# Lemming_SMD_2_2.net
KiCad netlist of a schematic drawn in EAGLE
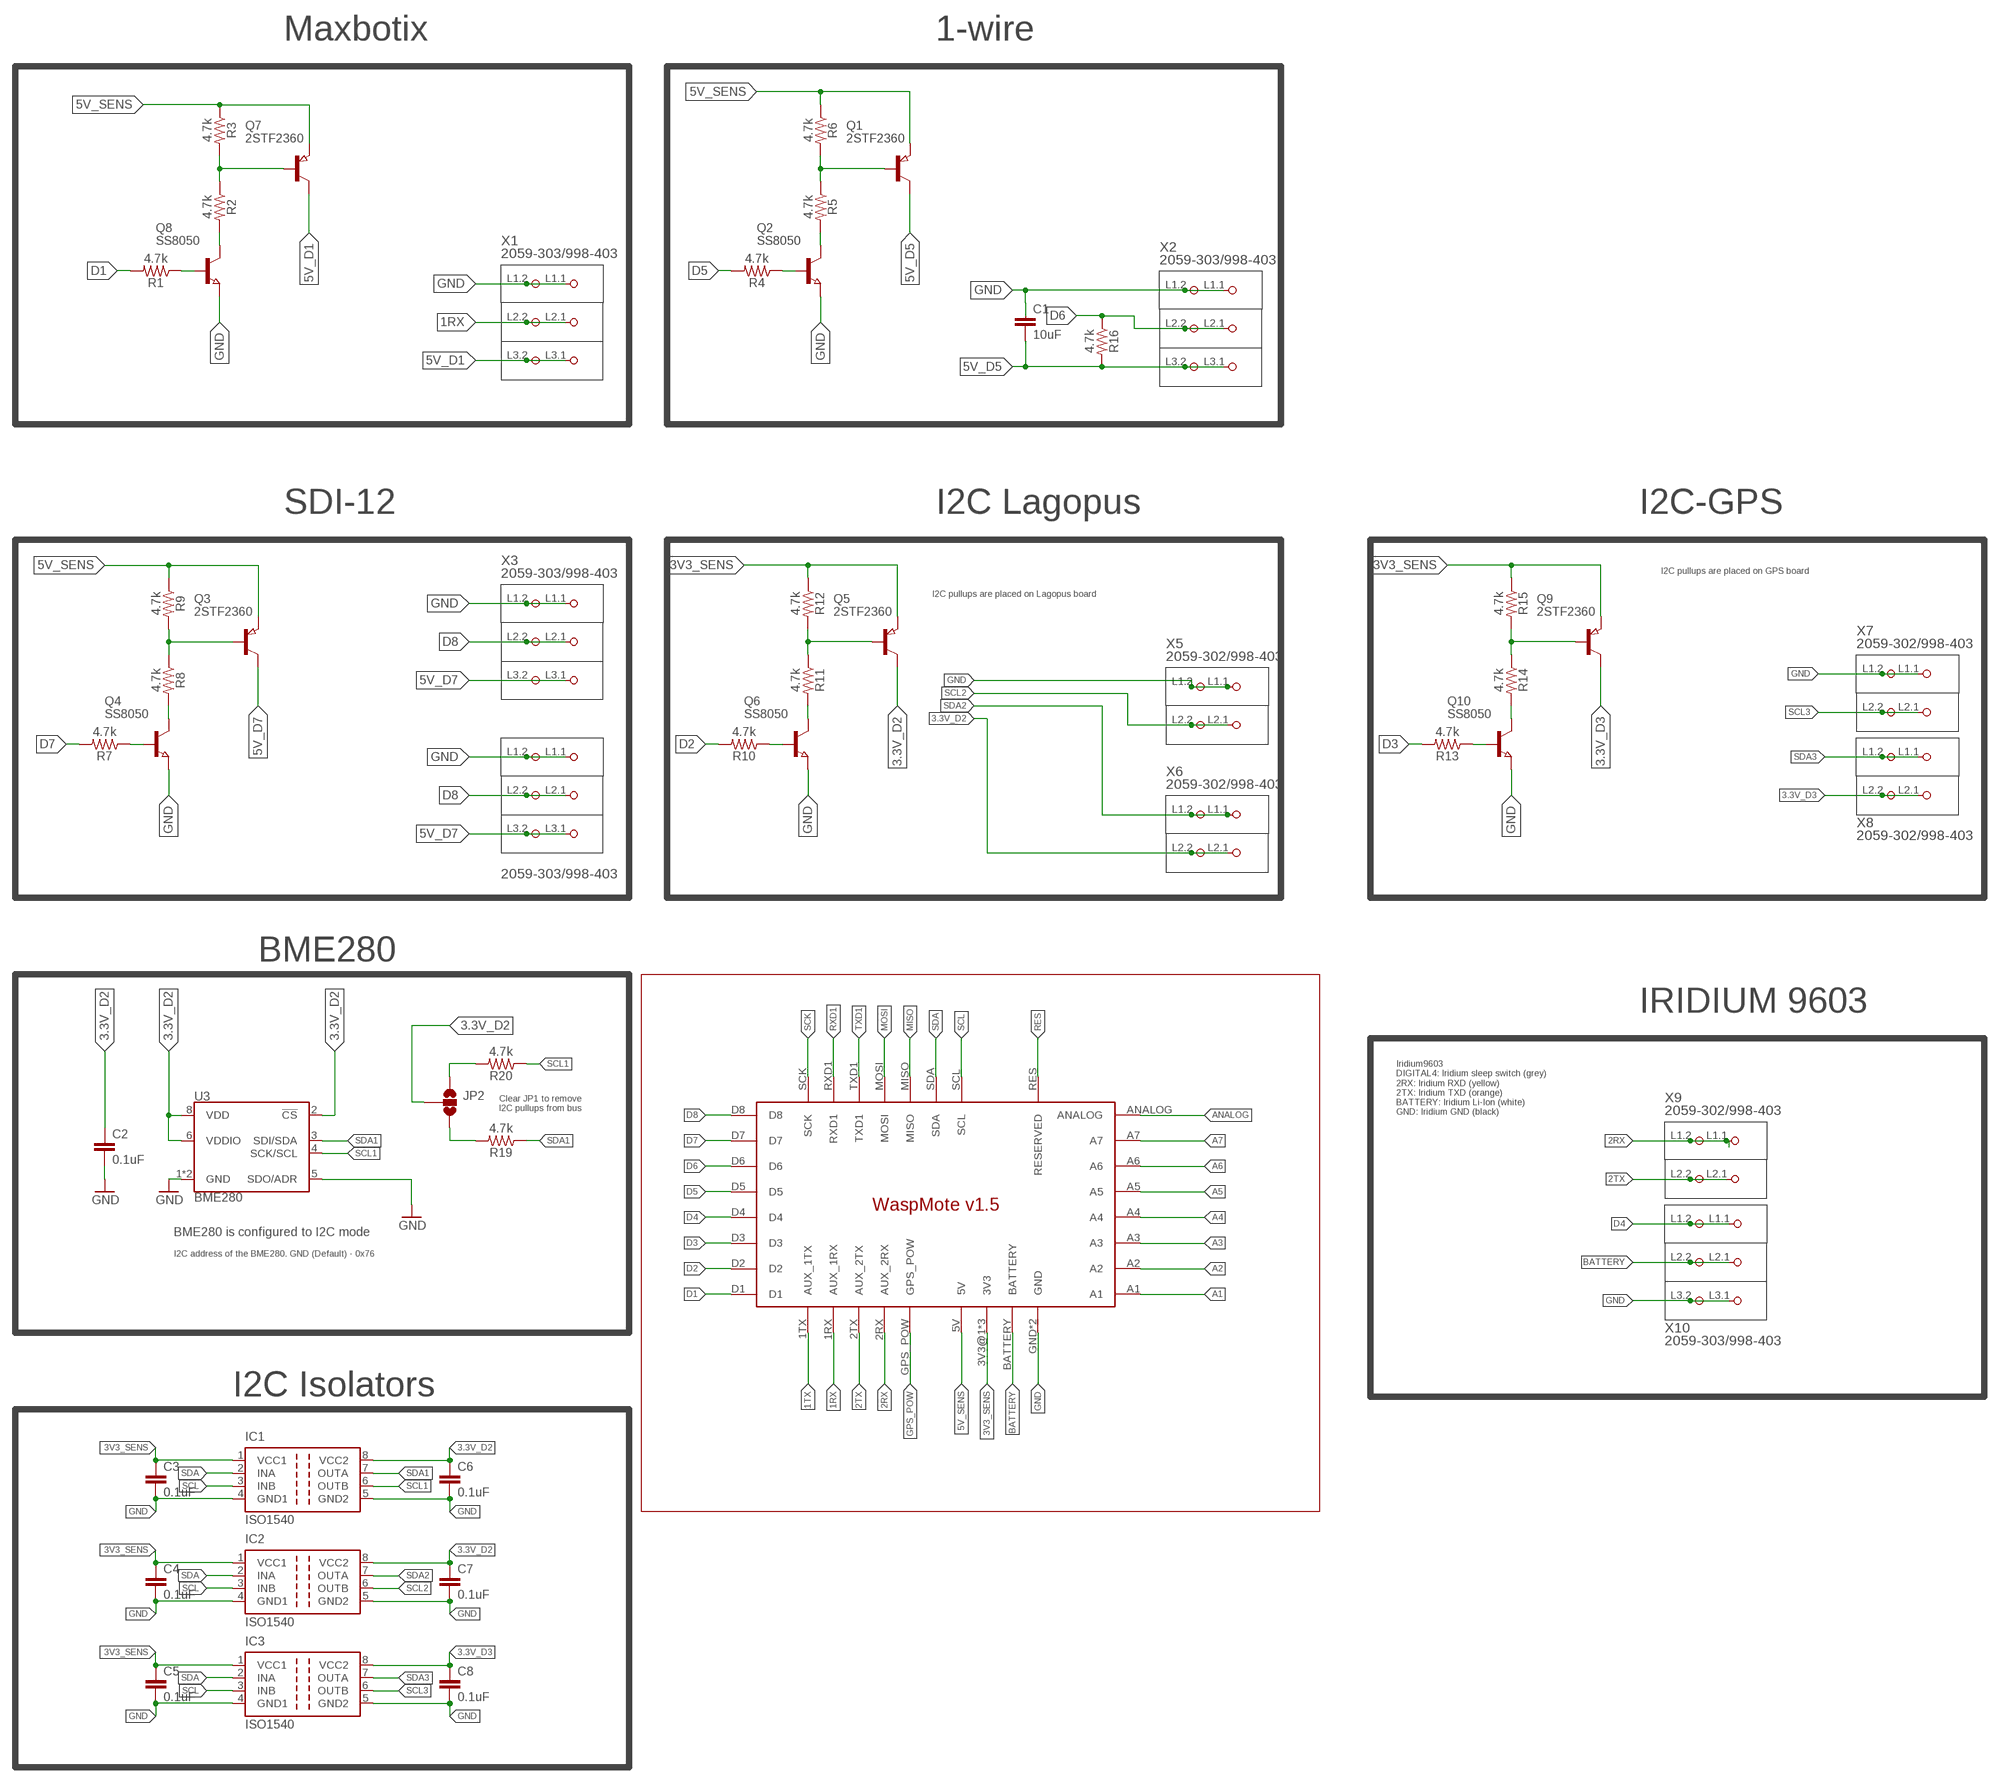
[diagram p0: schematic, sheet 1]

(export (version "E")
  (design (tool "Eeschema 10.0.6"))
  (components
    (comp (ref "C1")
      (value "10uF")
      (footprint "eagle-import:0603")
      (libsource (lib "eagle-import") (part "10UF-0603-6.3V-20%"))
    )
    (comp (ref "C2")
      (value "0.1uF")
      (footprint "eagle-import:0603")
      (libsource (lib "eagle-import") (part "0.1UF-0603-25V-(+80/-20%)"))
    )
    (comp (ref "C3")
      (value "0.1uF")
      (footprint "eagle-import:0603")
      (libsource (lib "eagle-import") (part "0.1UF-0603-25V-(+80/-20%)"))
    )
    (comp (ref "C4")
      (value "0.1uF")
      (footprint "eagle-import:0603")
      (libsource (lib "eagle-import") (part "0.1UF-0603-25V-(+80/-20%)"))
    )
    (comp (ref "C5")
      (value "0.1uF")
      (footprint "eagle-import:0603")
      (libsource (lib "eagle-import") (part "0.1UF-0603-25V-(+80/-20%)"))
    )
    (comp (ref "C6")
      (value "0.1uF")
      (footprint "eagle-import:0603")
      (libsource (lib "eagle-import") (part "0.1UF-0603-25V-(+80/-20%)"))
    )
    (comp (ref "C7")
      (value "0.1uF")
      (footprint "eagle-import:0603")
      (libsource (lib "eagle-import") (part "0.1UF-0603-25V-(+80/-20%)"))
    )
    (comp (ref "C8")
      (value "0.1uF")
      (footprint "eagle-import:0603")
      (libsource (lib "eagle-import") (part "0.1UF-0603-25V-(+80/-20%)"))
    )
    (comp (ref "IC1")
      (value "ISO1540")
      (footprint "eagle-import:SO-08")
      (fields (field (name "MPN") "ISO7220MD"))
      (libsource (lib "eagle-import") (part "ISO7220M"))
    )
    (comp (ref "IC2")
      (value "ISO1540")
      (footprint "eagle-import:SO-08")
      (fields (field (name "MPN") "ISO7220MD"))
      (libsource (lib "eagle-import") (part "ISO7220M"))
    )
    (comp (ref "IC3")
      (value "ISO1540")
      (footprint "eagle-import:SO-08")
      (fields (field (name "MPN") "ISO7220MD"))
      (libsource (lib "eagle-import") (part "ISO7220M"))
    )
    (comp (ref "JP2")
      (value "JUMPER-SMT_3_NO_SILK")
      (footprint "eagle-import:SMT-JUMPER_3_NO_SILK")
      (libsource (lib "eagle-import") (part "JUMPER-SMT_3_NO_SILK"))
    )
    (comp (ref "Q1")
      (value "2STF2360")
      (footprint "eagle-import:SOT89")
      (libsource (lib "eagle-import") (part "PNP-TRANSISTOR_SOT89"))
    )
    (comp (ref "Q2")
      (value "SS8050")
      (footprint "eagle-import:SOT23")
      (libsource (lib "eagle-import") (part "NPN-TRANSISTOR_SOT23"))
    )
    (comp (ref "Q3")
      (value "2STF2360")
      (footprint "eagle-import:SOT89")
      (libsource (lib "eagle-import") (part "PNP-TRANSISTOR_SOT89"))
    )
    (comp (ref "Q4")
      (value "SS8050")
      (footprint "eagle-import:SOT23")
      (libsource (lib "eagle-import") (part "NPN-TRANSISTOR_SOT23"))
    )
    (comp (ref "Q5")
      (value "2STF2360")
      (footprint "eagle-import:SOT89")
      (libsource (lib "eagle-import") (part "PNP-TRANSISTOR_SOT89"))
    )
    (comp (ref "Q6")
      (value "SS8050")
      (footprint "eagle-import:SOT23")
      (libsource (lib "eagle-import") (part "NPN-TRANSISTOR_SOT23"))
    )
    (comp (ref "Q7")
      (value "2STF2360")
      (footprint "eagle-import:SOT89")
      (libsource (lib "eagle-import") (part "PNP-TRANSISTOR_SOT89"))
    )
    (comp (ref "Q8")
      (value "SS8050")
      (footprint "eagle-import:SOT23")
      (libsource (lib "eagle-import") (part "NPN-TRANSISTOR_SOT23"))
    )
    (comp (ref "Q9")
      (value "2STF2360")
      (footprint "eagle-import:SOT89")
      (libsource (lib "eagle-import") (part "PNP-TRANSISTOR_SOT89"))
    )
    (comp (ref "Q10")
      (value "SS8050")
      (footprint "eagle-import:SOT23")
      (libsource (lib "eagle-import") (part "NPN-TRANSISTOR_SOT23"))
    )
    (comp (ref "R1")
      (value "4.7k")
      (footprint "eagle-import:0603")
      (libsource (lib "eagle-import") (part "4.7KOHM-0603-1/10W-1%"))
    )
    (comp (ref "R2")
      (value "4.7k")
      (footprint "eagle-import:0603")
      (libsource (lib "eagle-import") (part "4.7KOHM-0603-1/10W-1%"))
    )
    (comp (ref "R3")
      (value "4.7k")
      (footprint "eagle-import:0603")
      (libsource (lib "eagle-import") (part "4.7KOHM-0603-1/10W-1%"))
    )
    (comp (ref "R4")
      (value "4.7k")
      (footprint "eagle-import:0603")
      (libsource (lib "eagle-import") (part "4.7KOHM-0603-1/10W-1%"))
    )
    (comp (ref "R5")
      (value "4.7k")
      (footprint "eagle-import:0603")
      (libsource (lib "eagle-import") (part "4.7KOHM-0603-1/10W-1%"))
    )
    (comp (ref "R6")
      (value "4.7k")
      (footprint "eagle-import:0603")
      (libsource (lib "eagle-import") (part "4.7KOHM-0603-1/10W-1%"))
    )
    (comp (ref "R7")
      (value "4.7k")
      (footprint "eagle-import:0603")
      (libsource (lib "eagle-import") (part "4.7KOHM-0603-1/10W-1%"))
    )
    (comp (ref "R8")
      (value "4.7k")
      (footprint "eagle-import:0603")
      (libsource (lib "eagle-import") (part "4.7KOHM-0603-1/10W-1%"))
    )
    (comp (ref "R9")
      (value "4.7k")
      (footprint "eagle-import:0603")
      (libsource (lib "eagle-import") (part "4.7KOHM-0603-1/10W-1%"))
    )
    (comp (ref "R10")
      (value "4.7k")
      (footprint "eagle-import:0603")
      (libsource (lib "eagle-import") (part "4.7KOHM-0603-1/10W-1%"))
    )
    (comp (ref "R11")
      (value "4.7k")
      (footprint "eagle-import:0603")
      (libsource (lib "eagle-import") (part "4.7KOHM-0603-1/10W-1%"))
    )
    (comp (ref "R12")
      (value "4.7k")
      (footprint "eagle-import:0603")
      (libsource (lib "eagle-import") (part "4.7KOHM-0603-1/10W-1%"))
    )
    (comp (ref "R13")
      (value "4.7k")
      (footprint "eagle-import:0603")
      (libsource (lib "eagle-import") (part "4.7KOHM-0603-1/10W-1%"))
    )
    (comp (ref "R14")
      (value "4.7k")
      (footprint "eagle-import:0603")
      (libsource (lib "eagle-import") (part "4.7KOHM-0603-1/10W-1%"))
    )
    (comp (ref "R15")
      (value "4.7k")
      (footprint "eagle-import:0603")
      (libsource (lib "eagle-import") (part "4.7KOHM-0603-1/10W-1%"))
    )
    (comp (ref "R16")
      (value "4.7k")
      (footprint "eagle-import:0603")
      (libsource (lib "eagle-import") (part "4.7KOHM-0603-1/10W-1%"))
    )
    (comp (ref "R19")
      (value "4.7k")
      (footprint "eagle-import:0603")
      (libsource (lib "eagle-import") (part "4.7KOHM-0603-1/10W-1%"))
    )
    (comp (ref "R20")
      (value "4.7k")
      (footprint "eagle-import:0603")
      (libsource (lib "eagle-import") (part "4.7KOHM-0603-1/10W-1%"))
    )
    (comp (ref "U$1")
      (value "WASPMOTE_V1.5")
      (footprint "eagle-import:WASPMOTE_V1.5")
      (libsource (lib "eagle-import") (part "WASPMOTE_V1.5"))
    )
    (comp (ref "U3")
      (value "BME280")
      (footprint "eagle-import:LGA-8-2.5X2.5")
      (libsource (lib "eagle-import") (part "BME280"))
    )
    (comp (ref "X1")
      (value "2059-303/998-403")
      (footprint "eagle-import:P-2059-303_998-403")
      (libsource (lib "eagle-import") (part "2059-303/998-403"))
    )
    (comp (ref "X2")
      (value "2059-303/998-403")
      (footprint "eagle-import:P-2059-303_998-403")
      (libsource (lib "eagle-import") (part "2059-303/998-403"))
    )
    (comp (ref "X3")
      (value "2059-303/998-403")
      (footprint "eagle-import:P-2059-303_998-403")
      (libsource (lib "eagle-import") (part "2059-303/998-403"))
    )
    (comp (ref "X4")
      (value "2059-303/998-403")
      (footprint "eagle-import:P-2059-303_998-403")
      (libsource (lib "eagle-import") (part "2059-303/998-403"))
    )
    (comp (ref "X5")
      (value "2059-302/998-403")
      (footprint "eagle-import:P-2059-302_998-403")
      (libsource (lib "eagle-import") (part "2059-302/998-403"))
    )
    (comp (ref "X6")
      (value "2059-302/998-403")
      (footprint "eagle-import:P-2059-302_998-403")
      (libsource (lib "eagle-import") (part "2059-302/998-403"))
    )
    (comp (ref "X7")
      (value "2059-302/998-403")
      (footprint "eagle-import:P-2059-302_998-403")
      (libsource (lib "eagle-import") (part "2059-302/998-403"))
    )
    (comp (ref "X8")
      (value "2059-302/998-403")
      (footprint "eagle-import:P-2059-302_998-403")
      (libsource (lib "eagle-import") (part "2059-302/998-403"))
    )
    (comp (ref "X9")
      (value "2059-302/998-403")
      (footprint "eagle-import:P-2059-302_998-403")
      (libsource (lib "eagle-import") (part "2059-302/998-403"))
    )
    (comp (ref "X10")
      (value "2059-303/998-403")
      (footprint "eagle-import:P-2059-303_998-403")
      (libsource (lib "eagle-import") (part "2059-303/998-403"))
    )
  )
  (nets
    (net (code "1") (name "1RX") (class "Default")
      (node (ref "U$1") (pin "1RX") (pinfunction "AUX_1RX_1RX") (pintype "bidirectional"))
      (node (ref "X1") (pin "L2.1") (pinfunction "P2.1_L2.1") (pintype "bidirectional"))
      (node (ref "X1") (pin "L2.2") (pinfunction "P2.2_L2.2") (pintype "bidirectional"))
    )
    (net (code "2") (name "1TX") (class "Default")
      (node (ref "U$1") (pin "1TX") (pinfunction "AUX_1TX_1TX") (pintype "bidirectional"))
    )
    (net (code "3") (name "2RX") (class "Default")
      (node (ref "U$1") (pin "2RX") (pinfunction "AUX_2RX_2RX") (pintype "bidirectional"))
      (node (ref "X9") (pin "L1.1") (pinfunction "P1.1_L1.1") (pintype "bidirectional"))
      (node (ref "X9") (pin "L1.2") (pinfunction "P1.2_L1.2") (pintype "bidirectional"))
    )
    (net (code "4") (name "2TX") (class "Default")
      (node (ref "U$1") (pin "2TX") (pinfunction "AUX_2TX_2TX") (pintype "bidirectional"))
      (node (ref "X9") (pin "L2.1") (pinfunction "P2.1_L2.1") (pintype "bidirectional"))
      (node (ref "X9") (pin "L2.2") (pinfunction "P2.2_L2.2") (pintype "bidirectional"))
    )
    (net (code "5") (name "3.3V_D2") (class "Default")
      (node (ref "C2") (pin "1") (pinfunction "1_1") (pintype "passive"))
      (node (ref "C6") (pin "1") (pinfunction "1_1") (pintype "passive"))
      (node (ref "C7") (pin "1") (pinfunction "1_1") (pintype "passive"))
      (node (ref "IC1") (pin "8") (pinfunction "VCC2_8") (pintype "power_in"))
      (node (ref "IC2") (pin "8") (pinfunction "VCC2_8") (pintype "power_in"))
      (node (ref "JP2") (pin "2") (pinfunction "2_2") (pintype "passive"))
      (node (ref "Q5") (pin "2") (pinfunction "C_2") (pintype "passive"))
      (node (ref "U3") (pin "2") (pinfunction "~{CS}_2") (pintype "bidirectional"))
      (node (ref "U3") (pin "6") (pinfunction "VDDIO_6") (pintype "bidirectional"))
      (node (ref "U3") (pin "8") (pinfunction "VDD_8") (pintype "bidirectional"))
      (node (ref "X6") (pin "L2.1") (pinfunction "P2.1_L2.1") (pintype "bidirectional"))
      (node (ref "X6") (pin "L2.2") (pinfunction "P2.2_L2.2") (pintype "bidirectional"))
    )
    (net (code "6") (name "3.3V_D3") (class "Default")
      (node (ref "C8") (pin "1") (pinfunction "1_1") (pintype "passive"))
      (node (ref "IC3") (pin "8") (pinfunction "VCC2_8") (pintype "power_in"))
      (node (ref "Q9") (pin "2") (pinfunction "C_2") (pintype "passive"))
      (node (ref "X8") (pin "L2.1") (pinfunction "P2.1_L2.1") (pintype "bidirectional"))
      (node (ref "X8") (pin "L2.2") (pinfunction "P2.2_L2.2") (pintype "bidirectional"))
    )
    (net (code "7") (name "3V3_SENS") (class "Default")
      (node (ref "C3") (pin "1") (pinfunction "1_1") (pintype "passive"))
      (node (ref "C4") (pin "1") (pinfunction "1_1") (pintype "passive"))
      (node (ref "C5") (pin "1") (pinfunction "1_1") (pintype "passive"))
      (node (ref "IC1") (pin "1") (pinfunction "VCC1_1") (pintype "power_in"))
      (node (ref "IC2") (pin "1") (pinfunction "VCC1_1") (pintype "power_in"))
      (node (ref "IC3") (pin "1") (pinfunction "VCC1_1") (pintype "power_in"))
      (node (ref "Q5") (pin "3") (pinfunction "E_3") (pintype "passive"))
      (node (ref "Q9") (pin "3") (pinfunction "E_3") (pintype "passive"))
      (node (ref "R12") (pin "1") (pinfunction "1_1") (pintype "passive"))
      (node (ref "R15") (pin "1") (pinfunction "1_1") (pintype "passive"))
      (node (ref "U$1") (pin "3V3@1") (pinfunction "3V3_3V3@1") (pintype "bidirectional"))
      (node (ref "U$1") (pin "3V3@2") (pinfunction "3V3_3V3@2") (pintype "bidirectional"))
      (node (ref "U$1") (pin "3V3@3") (pinfunction "3V3_3V3@3") (pintype "bidirectional"))
    )
    (net (code "8") (name "5V_D1") (class "Default")
      (node (ref "Q7") (pin "2") (pinfunction "C_2") (pintype "passive"))
      (node (ref "X1") (pin "L3.1") (pinfunction "P3.1_L3.1") (pintype "bidirectional"))
      (node (ref "X1") (pin "L3.2") (pinfunction "P3.2_L3.2") (pintype "bidirectional"))
    )
    (net (code "9") (name "5V_D5") (class "Default")
      (node (ref "C1") (pin "2") (pinfunction "2_2") (pintype "passive"))
      (node (ref "Q1") (pin "2") (pinfunction "C_2") (pintype "passive"))
      (node (ref "R16") (pin "2") (pinfunction "2_2") (pintype "passive"))
      (node (ref "X2") (pin "L3.1") (pinfunction "P3.1_L3.1") (pintype "bidirectional"))
      (node (ref "X2") (pin "L3.2") (pinfunction "P3.2_L3.2") (pintype "bidirectional"))
    )
    (net (code "10") (name "5V_D7") (class "Default")
      (node (ref "Q3") (pin "2") (pinfunction "C_2") (pintype "passive"))
      (node (ref "X3") (pin "L3.1") (pinfunction "P3.1_L3.1") (pintype "bidirectional"))
      (node (ref "X3") (pin "L3.2") (pinfunction "P3.2_L3.2") (pintype "bidirectional"))
      (node (ref "X4") (pin "L3.1") (pinfunction "P3.1_L3.1") (pintype "bidirectional"))
      (node (ref "X4") (pin "L3.2") (pinfunction "P3.2_L3.2") (pintype "bidirectional"))
    )
    (net (code "11") (name "5V_SENS") (class "Default")
      (node (ref "Q1") (pin "3") (pinfunction "E_3") (pintype "passive"))
      (node (ref "Q3") (pin "3") (pinfunction "E_3") (pintype "passive"))
      (node (ref "Q7") (pin "3") (pinfunction "E_3") (pintype "passive"))
      (node (ref "R3") (pin "1") (pinfunction "1_1") (pintype "passive"))
      (node (ref "R6") (pin "1") (pinfunction "1_1") (pintype "passive"))
      (node (ref "R9") (pin "1") (pinfunction "1_1") (pintype "passive"))
      (node (ref "U$1") (pin "5V") (pinfunction "5V_5V") (pintype "bidirectional"))
    )
    (net (code "12") (name "A1") (class "Default")
      (node (ref "U$1") (pin "A1") (pinfunction "A1_A1") (pintype "bidirectional"))
    )
    (net (code "13") (name "A2") (class "Default")
      (node (ref "U$1") (pin "A2") (pinfunction "A2_A2") (pintype "bidirectional"))
    )
    (net (code "14") (name "A3") (class "Default")
      (node (ref "U$1") (pin "A3") (pinfunction "A3_A3") (pintype "bidirectional"))
    )
    (net (code "15") (name "A4") (class "Default")
      (node (ref "U$1") (pin "A4") (pinfunction "A4_A4") (pintype "bidirectional"))
    )
    (net (code "16") (name "A5") (class "Default")
      (node (ref "U$1") (pin "A5") (pinfunction "A5_A5") (pintype "bidirectional"))
    )
    (net (code "17") (name "A6") (class "Default")
      (node (ref "U$1") (pin "A6") (pinfunction "A6_A6") (pintype "bidirectional"))
    )
    (net (code "18") (name "A7") (class "Default")
      (node (ref "U$1") (pin "A7") (pinfunction "A7_A7") (pintype "bidirectional"))
    )
    (net (code "19") (name "ANALOG") (class "Default")
      (node (ref "U$1") (pin "ANALOG") (pinfunction "ANALOG_ANALOG") (pintype "bidirectional"))
    )
    (net (code "20") (name "BATTERY") (class "Default")
      (node (ref "U$1") (pin "BATTERY") (pinfunction "BATTERY_BATTERY") (pintype "bidirectional"))
      (node (ref "X10") (pin "L2.1") (pinfunction "P2.1_L2.1") (pintype "bidirectional"))
      (node (ref "X10") (pin "L2.2") (pinfunction "P2.2_L2.2") (pintype "bidirectional"))
    )
    (net (code "21") (name "D1") (class "Default")
      (node (ref "R1") (pin "2") (pinfunction "2_2") (pintype "passive"))
      (node (ref "U$1") (pin "D1") (pinfunction "D1_D1") (pintype "bidirectional"))
    )
    (net (code "22") (name "D2") (class "Default")
      (node (ref "R10") (pin "2") (pinfunction "2_2") (pintype "passive"))
      (node (ref "U$1") (pin "D2") (pinfunction "D2_D2") (pintype "bidirectional"))
    )
    (net (code "23") (name "D3") (class "Default")
      (node (ref "R13") (pin "2") (pinfunction "2_2") (pintype "passive"))
      (node (ref "U$1") (pin "D3") (pinfunction "D3_D3") (pintype "bidirectional"))
    )
    (net (code "24") (name "D4") (class "Default")
      (node (ref "U$1") (pin "D4") (pinfunction "D4_D4") (pintype "bidirectional"))
      (node (ref "X10") (pin "L1.1") (pinfunction "P1.1_L1.1") (pintype "bidirectional"))
      (node (ref "X10") (pin "L1.2") (pinfunction "P1.2_L1.2") (pintype "bidirectional"))
    )
    (net (code "25") (name "D5") (class "Default")
      (node (ref "R4") (pin "2") (pinfunction "2_2") (pintype "passive"))
      (node (ref "U$1") (pin "D5") (pinfunction "D5_D5") (pintype "bidirectional"))
    )
    (net (code "26") (name "D6") (class "Default")
      (node (ref "R16") (pin "1") (pinfunction "1_1") (pintype "passive"))
      (node (ref "U$1") (pin "D6") (pinfunction "D6_D6") (pintype "bidirectional"))
      (node (ref "X2") (pin "L2.1") (pinfunction "P2.1_L2.1") (pintype "bidirectional"))
      (node (ref "X2") (pin "L2.2") (pinfunction "P2.2_L2.2") (pintype "bidirectional"))
    )
    (net (code "27") (name "D7") (class "Default")
      (node (ref "R7") (pin "2") (pinfunction "2_2") (pintype "passive"))
      (node (ref "U$1") (pin "D7") (pinfunction "D7_D7") (pintype "bidirectional"))
    )
    (net (code "28") (name "D8") (class "Default")
      (node (ref "U$1") (pin "D8") (pinfunction "D8_D8") (pintype "bidirectional"))
      (node (ref "X3") (pin "L2.1") (pinfunction "P2.1_L2.1") (pintype "bidirectional"))
      (node (ref "X3") (pin "L2.2") (pinfunction "P2.2_L2.2") (pintype "bidirectional"))
      (node (ref "X4") (pin "L2.1") (pinfunction "P2.1_L2.1") (pintype "bidirectional"))
      (node (ref "X4") (pin "L2.2") (pinfunction "P2.2_L2.2") (pintype "bidirectional"))
    )
    (net (code "29") (name "GND") (class "Default")
      (node (ref "C1") (pin "1") (pinfunction "1_1") (pintype "passive"))
      (node (ref "C2") (pin "2") (pinfunction "2_2") (pintype "passive"))
      (node (ref "C3") (pin "2") (pinfunction "2_2") (pintype "passive"))
      (node (ref "C4") (pin "2") (pinfunction "2_2") (pintype "passive"))
      (node (ref "C5") (pin "2") (pinfunction "2_2") (pintype "passive"))
      (node (ref "C6") (pin "2") (pinfunction "2_2") (pintype "passive"))
      (node (ref "C7") (pin "2") (pinfunction "2_2") (pintype "passive"))
      (node (ref "C8") (pin "2") (pinfunction "2_2") (pintype "passive"))
      (node (ref "IC1") (pin "4") (pinfunction "GND1_4") (pintype "power_in"))
      (node (ref "IC1") (pin "5") (pinfunction "GND2_5") (pintype "power_in"))
      (node (ref "IC2") (pin "4") (pinfunction "GND1_4") (pintype "power_in"))
      (node (ref "IC2") (pin "5") (pinfunction "GND2_5") (pintype "power_in"))
      (node (ref "IC3") (pin "4") (pinfunction "GND1_4") (pintype "power_in"))
      (node (ref "IC3") (pin "5") (pinfunction "GND2_5") (pintype "power_in"))
      (node (ref "Q10") (pin "2") (pinfunction "E_2") (pintype "passive"))
      (node (ref "Q2") (pin "2") (pinfunction "E_2") (pintype "passive"))
      (node (ref "Q4") (pin "2") (pinfunction "E_2") (pintype "passive"))
      (node (ref "Q6") (pin "2") (pinfunction "E_2") (pintype "passive"))
      (node (ref "Q8") (pin "2") (pinfunction "E_2") (pintype "passive"))
      (node (ref "U$1") (pin "GND") (pinfunction "GND_GND") (pintype "bidirectional"))
      (node (ref "U$1") (pin "GND_2") (pinfunction "GND_GND_2") (pintype "bidirectional"))
      (node (ref "U3") (pin "1") (pinfunction "GND_1") (pintype "bidirectional"))
      (node (ref "U3") (pin "5") (pinfunction "SDO/ADR_5") (pintype "bidirectional"))
      (node (ref "U3") (pin "7") (pinfunction "GND_7") (pintype "bidirectional"))
      (node (ref "X1") (pin "L1.1") (pinfunction "P1.1_L1.1") (pintype "bidirectional"))
      (node (ref "X1") (pin "L1.2") (pinfunction "P1.2_L1.2") (pintype "bidirectional"))
      (node (ref "X10") (pin "L3.1") (pinfunction "P3.1_L3.1") (pintype "bidirectional"))
      (node (ref "X10") (pin "L3.2") (pinfunction "P3.2_L3.2") (pintype "bidirectional"))
      (node (ref "X2") (pin "L1.1") (pinfunction "P1.1_L1.1") (pintype "bidirectional"))
      (node (ref "X2") (pin "L1.2") (pinfunction "P1.2_L1.2") (pintype "bidirectional"))
      (node (ref "X3") (pin "L1.1") (pinfunction "P1.1_L1.1") (pintype "bidirectional"))
      (node (ref "X3") (pin "L1.2") (pinfunction "P1.2_L1.2") (pintype "bidirectional"))
      (node (ref "X4") (pin "L1.1") (pinfunction "P1.1_L1.1") (pintype "bidirectional"))
      (node (ref "X4") (pin "L1.2") (pinfunction "P1.2_L1.2") (pintype "bidirectional"))
      (node (ref "X5") (pin "L1.1") (pinfunction "P1.1_L1.1") (pintype "bidirectional"))
      (node (ref "X5") (pin "L1.2") (pinfunction "P1.2_L1.2") (pintype "bidirectional"))
      (node (ref "X7") (pin "L1.1") (pinfunction "P1.1_L1.1") (pintype "bidirectional"))
      (node (ref "X7") (pin "L1.2") (pinfunction "P1.2_L1.2") (pintype "bidirectional"))
    )
    (net (code "30") (name "GPS_POW") (class "Default")
      (node (ref "U$1") (pin "GPS_POW") (pinfunction "GPS_POW_GPS_POW") (pintype "bidirectional"))
    )
    (net (code "31") (name "MISO") (class "Default")
      (node (ref "U$1") (pin "MISO") (pinfunction "MISO_MISO") (pintype "bidirectional"))
    )
    (net (code "32") (name "MOSI") (class "Default")
      (node (ref "U$1") (pin "MOSI") (pinfunction "MOSI_MOSI") (pintype "bidirectional"))
    )
    (net (code "33") (name "Net-(JP2-Pad1)") (class "Default")
      (node (ref "JP2") (pin "1") (pinfunction "1_1") (pintype "passive"))
      (node (ref "R20") (pin "2") (pinfunction "2_2") (pintype "passive"))
    )
    (net (code "34") (name "Net-(JP2-Pad3)") (class "Default")
      (node (ref "JP2") (pin "3") (pinfunction "3_3") (pintype "passive"))
      (node (ref "R19") (pin "2") (pinfunction "2_2") (pintype "passive"))
    )
    (net (code "35") (name "Net-(Q1-B)") (class "Default")
      (node (ref "Q1") (pin "1") (pinfunction "B_1") (pintype "passive"))
      (node (ref "R5") (pin "1") (pinfunction "1_1") (pintype "passive"))
      (node (ref "R6") (pin "2") (pinfunction "2_2") (pintype "passive"))
    )
    (net (code "36") (name "Net-(Q2-B)") (class "Default")
      (node (ref "Q2") (pin "1") (pinfunction "B_1") (pintype "passive"))
      (node (ref "R4") (pin "1") (pinfunction "1_1") (pintype "passive"))
    )
    (net (code "37") (name "Net-(Q2-C)") (class "Default")
      (node (ref "Q2") (pin "3") (pinfunction "C_3") (pintype "passive"))
      (node (ref "R5") (pin "2") (pinfunction "2_2") (pintype "passive"))
    )
    (net (code "38") (name "Net-(Q3-B)") (class "Default")
      (node (ref "Q3") (pin "1") (pinfunction "B_1") (pintype "passive"))
      (node (ref "R8") (pin "1") (pinfunction "1_1") (pintype "passive"))
      (node (ref "R9") (pin "2") (pinfunction "2_2") (pintype "passive"))
    )
    (net (code "39") (name "Net-(Q4-B)") (class "Default")
      (node (ref "Q4") (pin "1") (pinfunction "B_1") (pintype "passive"))
      (node (ref "R7") (pin "1") (pinfunction "1_1") (pintype "passive"))
    )
    (net (code "40") (name "Net-(Q4-C)") (class "Default")
      (node (ref "Q4") (pin "3") (pinfunction "C_3") (pintype "passive"))
      (node (ref "R8") (pin "2") (pinfunction "2_2") (pintype "passive"))
    )
    (net (code "41") (name "Net-(Q5-B)") (class "Default")
      (node (ref "Q5") (pin "1") (pinfunction "B_1") (pintype "passive"))
      (node (ref "R11") (pin "1") (pinfunction "1_1") (pintype "passive"))
      (node (ref "R12") (pin "2") (pinfunction "2_2") (pintype "passive"))
    )
    (net (code "42") (name "Net-(Q6-B)") (class "Default")
      (node (ref "Q6") (pin "1") (pinfunction "B_1") (pintype "passive"))
      (node (ref "R10") (pin "1") (pinfunction "1_1") (pintype "passive"))
    )
    (net (code "43") (name "Net-(Q6-C)") (class "Default")
      (node (ref "Q6") (pin "3") (pinfunction "C_3") (pintype "passive"))
      (node (ref "R11") (pin "2") (pinfunction "2_2") (pintype "passive"))
    )
    (net (code "44") (name "Net-(Q7-B)") (class "Default")
      (node (ref "Q7") (pin "1") (pinfunction "B_1") (pintype "passive"))
      (node (ref "R2") (pin "1") (pinfunction "1_1") (pintype "passive"))
      (node (ref "R3") (pin "2") (pinfunction "2_2") (pintype "passive"))
    )
    (net (code "45") (name "Net-(Q8-B)") (class "Default")
      (node (ref "Q8") (pin "1") (pinfunction "B_1") (pintype "passive"))
      (node (ref "R1") (pin "1") (pinfunction "1_1") (pintype "passive"))
    )
    (net (code "46") (name "Net-(Q8-C)") (class "Default")
      (node (ref "Q8") (pin "3") (pinfunction "C_3") (pintype "passive"))
      (node (ref "R2") (pin "2") (pinfunction "2_2") (pintype "passive"))
    )
    (net (code "47") (name "Net-(Q9-B)") (class "Default")
      (node (ref "Q9") (pin "1") (pinfunction "B_1") (pintype "passive"))
      (node (ref "R14") (pin "1") (pinfunction "1_1") (pintype "passive"))
      (node (ref "R15") (pin "2") (pinfunction "2_2") (pintype "passive"))
    )
    (net (code "48") (name "Net-(Q10-B)") (class "Default")
      (node (ref "Q10") (pin "1") (pinfunction "B_1") (pintype "passive"))
      (node (ref "R13") (pin "1") (pinfunction "1_1") (pintype "passive"))
    )
    (net (code "49") (name "Net-(Q10-C)") (class "Default")
      (node (ref "Q10") (pin "3") (pinfunction "C_3") (pintype "passive"))
      (node (ref "R14") (pin "2") (pinfunction "2_2") (pintype "passive"))
    )
    (net (code "50") (name "RES") (class "Default")
      (node (ref "U$1") (pin "RES") (pinfunction "RESERVED_RES") (pintype "bidirectional"))
    )
    (net (code "51") (name "RXD1") (class "Default")
      (node (ref "U$1") (pin "RXD1") (pinfunction "RXD1_RXD1") (pintype "bidirectional"))
    )
    (net (code "52") (name "SCK") (class "Default")
      (node (ref "U$1") (pin "SCK") (pinfunction "SCK_SCK") (pintype "bidirectional"))
    )
    (net (code "53") (name "SCL") (class "Default")
      (node (ref "IC1") (pin "3") (pinfunction "INB_3") (pintype "input"))
      (node (ref "IC2") (pin "3") (pinfunction "INB_3") (pintype "input"))
      (node (ref "IC3") (pin "3") (pinfunction "INB_3") (pintype "input"))
      (node (ref "U$1") (pin "SCL") (pinfunction "SCL_SCL") (pintype "bidirectional"))
    )
    (net (code "54") (name "SCL1") (class "Default")
      (node (ref "IC1") (pin "6") (pinfunction "OUTB_6") (pintype "output"))
      (node (ref "R20") (pin "1") (pinfunction "1_1") (pintype "passive"))
      (node (ref "U3") (pin "4") (pinfunction "SCK/SCL_4") (pintype "bidirectional"))
    )
    (net (code "55") (name "SCL2") (class "Default")
      (node (ref "IC2") (pin "6") (pinfunction "OUTB_6") (pintype "output"))
      (node (ref "X5") (pin "L2.1") (pinfunction "P2.1_L2.1") (pintype "bidirectional"))
      (node (ref "X5") (pin "L2.2") (pinfunction "P2.2_L2.2") (pintype "bidirectional"))
    )
    (net (code "56") (name "SCL3") (class "Default")
      (node (ref "IC3") (pin "6") (pinfunction "OUTB_6") (pintype "output"))
      (node (ref "X7") (pin "L2.1") (pinfunction "P2.1_L2.1") (pintype "bidirectional"))
      (node (ref "X7") (pin "L2.2") (pinfunction "P2.2_L2.2") (pintype "bidirectional"))
    )
    (net (code "57") (name "SDA") (class "Default")
      (node (ref "IC1") (pin "2") (pinfunction "INA_2") (pintype "input"))
      (node (ref "IC2") (pin "2") (pinfunction "INA_2") (pintype "input"))
      (node (ref "IC3") (pin "2") (pinfunction "INA_2") (pintype "input"))
      (node (ref "U$1") (pin "SDA") (pinfunction "SDA_SDA") (pintype "bidirectional"))
    )
    (net (code "58") (name "SDA1") (class "Default")
      (node (ref "IC1") (pin "7") (pinfunction "OUTA_7") (pintype "output"))
      (node (ref "R19") (pin "1") (pinfunction "1_1") (pintype "passive"))
      (node (ref "U3") (pin "3") (pinfunction "SDI/SDA_3") (pintype "bidirectional"))
    )
    (net (code "59") (name "SDA2") (class "Default")
      (node (ref "IC2") (pin "7") (pinfunction "OUTA_7") (pintype "output"))
      (node (ref "X6") (pin "L1.1") (pinfunction "P1.1_L1.1") (pintype "bidirectional"))
      (node (ref "X6") (pin "L1.2") (pinfunction "P1.2_L1.2") (pintype "bidirectional"))
    )
    (net (code "60") (name "SDA3") (class "Default")
      (node (ref "IC3") (pin "7") (pinfunction "OUTA_7") (pintype "output"))
      (node (ref "X8") (pin "L1.1") (pinfunction "P1.1_L1.1") (pintype "bidirectional"))
      (node (ref "X8") (pin "L1.2") (pinfunction "P1.2_L1.2") (pintype "bidirectional"))
    )
    (net (code "61") (name "TXD1") (class "Default")
      (node (ref "U$1") (pin "TXD1") (pinfunction "TXD1_TXD1") (pintype "bidirectional"))
    )
  )
)
